# SparkFun_IR_Thermometer_Eval-MLX90614.net
KiCad netlist of a schematic drawn in EAGLE
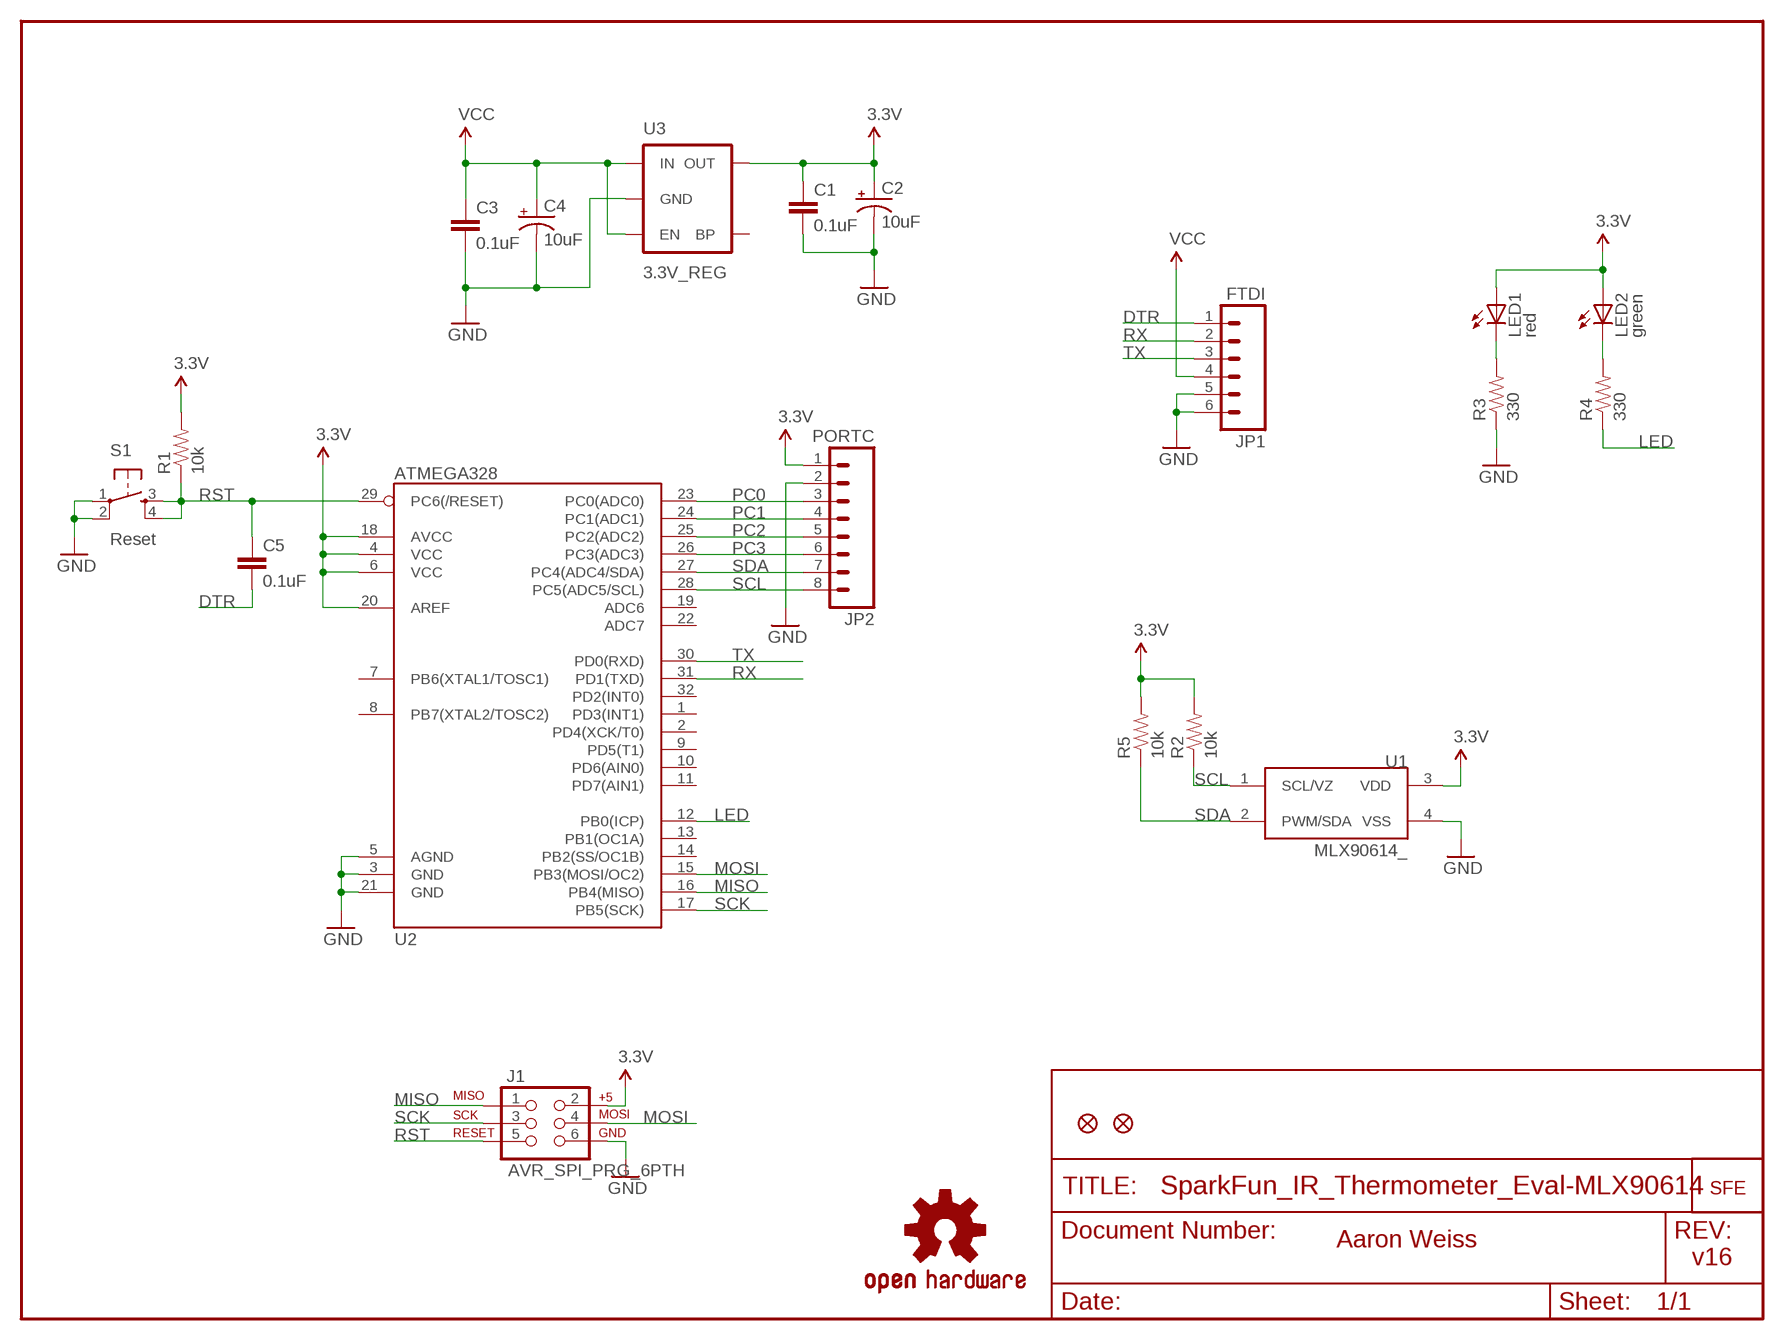
[diagram p0: schematic, sheet 1]

(export (version "E")
  (design (tool "Eeschema 10.0.6"))
  (components
    (comp (ref "C1")
      (value "0.1uF")
      (footprint "eagle-import:0402-CAP")
      (libsource (lib "eagle-import") (part "CAP0402-CAP"))
    )
    (comp (ref "C2")
      (value "10uF")
      (footprint "eagle-import:EIA3216")
      (libsource (lib "eagle-import") (part "CAP_POL1206"))
    )
    (comp (ref "C3")
      (value "0.1uF")
      (footprint "eagle-import:0402-CAP")
      (libsource (lib "eagle-import") (part "CAP0402-CAP"))
    )
    (comp (ref "C4")
      (value "10uF")
      (footprint "eagle-import:EIA3216")
      (libsource (lib "eagle-import") (part "CAP_POL1206"))
    )
    (comp (ref "C5")
      (value "0.1uF")
      (footprint "eagle-import:0402-CAP")
      (libsource (lib "eagle-import") (part "CAP0402-CAP"))
    )
    (comp (ref "J1")
      (value "AVR_SPI_PRG_6PTH")
      (footprint "eagle-import:2X3")
      (libsource (lib "eagle-import") (part "AVR_SPI_PRG_6PTH"))
    )
    (comp (ref "JP1")
      (value "FTDI")
      (footprint "eagle-import:1X06")
      (libsource (lib "eagle-import") (part "M06SIP"))
    )
    (comp (ref "JP2")
      (value "PORTC")
      (footprint "eagle-import:1X08")
      (libsource (lib "eagle-import") (part "M08"))
    )
    (comp (ref "JP3")
      (value "FIDUCIAL1X2.5")
      (footprint "eagle-import:FIDUCIAL-1X2.5")
      (libsource (lib "eagle-import") (part "FIDUCIAL1X2.5"))
    )
    (comp (ref "JP4")
      (value "LOGO-SFESK")
      (footprint "eagle-import:SFE-LOGO-FLAME")
      (libsource (lib "eagle-import") (part "LOGO-SFESK"))
    )
    (comp (ref "JP5")
      (value "FIDUCIAL1X2.5")
      (footprint "eagle-import:FIDUCIAL-1X2.5")
      (libsource (lib "eagle-import") (part "FIDUCIAL1X2.5"))
    )
    (comp (ref "LED1")
      (value "red")
      (footprint "eagle-import:LED-0603")
      (libsource (lib "eagle-import") (part "LED0603"))
    )
    (comp (ref "LED2")
      (value "green")
      (footprint "eagle-import:LED-0603")
      (libsource (lib "eagle-import") (part "LED0603"))
    )
    (comp (ref "R1")
      (value "10k")
      (footprint "eagle-import:0402-RES")
      (libsource (lib "eagle-import") (part "RESISTOR0402-RES"))
    )
    (comp (ref "R2")
      (value "10k")
      (footprint "eagle-import:0402-RES")
      (libsource (lib "eagle-import") (part "RESISTOR0402-RES"))
    )
    (comp (ref "R3")
      (value "330")
      (footprint "eagle-import:0402-RES")
      (libsource (lib "eagle-import") (part "RESISTOR0402-RES"))
    )
    (comp (ref "R4")
      (value "330")
      (footprint "eagle-import:0402-RES")
      (libsource (lib "eagle-import") (part "RESISTOR0402-RES"))
    )
    (comp (ref "R5")
      (value "10k")
      (footprint "eagle-import:0402-RES")
      (libsource (lib "eagle-import") (part "RESISTOR0402-RES"))
    )
    (comp (ref "S1")
      (value "Reset")
      (footprint "eagle-import:TACTILE_SWITCH_SMD")
      (libsource (lib "eagle-import") (part "TAC_SWITCHSMD"))
    )
    (comp (ref "U$1")
      (value "OSHW-LOGOS")
      (footprint "eagle-import:OSHW-LOGO-S")
      (libsource (lib "eagle-import") (part "OSHW-LOGOS"))
    )
    (comp (ref "U1")
      (value "MLX90614_")
      (footprint "eagle-import:TO-39")
      (libsource (lib "eagle-import") (part "MLX90614_"))
    )
    (comp (ref "U2")
      (value "ATMEGA328")
      (footprint "eagle-import:TQFP32-08")
      (libsource (lib "eagle-import") (part "ATMEGA168"))
    )
    (comp (ref "U3")
      (value "3.3V_REG")
      (footprint "eagle-import:SOT23-5")
      (libsource (lib "eagle-import") (part "V_REG_LDOSMD"))
    )
  )
  (nets
    (net (code "1") (name "/DTR") (class "Default")
      (node (ref "C5") (pin "2") (pinfunction "2_2") (pintype "passive"))
      (node (ref "JP1") (pin "1") (pinfunction "1_1") (pintype "passive"))
    )
    (net (code "2") (name "/LED") (class "Default")
      (node (ref "R4") (pin "1") (pinfunction "1_1") (pintype "passive"))
      (node (ref "U2") (pin "12") (pinfunction "PB0(ICP)_12") (pintype "bidirectional"))
    )
    (net (code "3") (name "/MISO") (class "Default")
      (node (ref "J1") (pin "1") (pinfunction "1_1") (pintype "passive"))
      (node (ref "U2") (pin "16") (pinfunction "PB4(MISO)_16") (pintype "bidirectional"))
    )
    (net (code "4") (name "/MOSI") (class "Default")
      (node (ref "J1") (pin "4") (pinfunction "4_4") (pintype "passive"))
      (node (ref "U2") (pin "15") (pinfunction "PB3(MOSI/OC2)_15") (pintype "bidirectional"))
    )
    (net (code "5") (name "/PC0") (class "Default")
      (node (ref "JP2") (pin "3") (pinfunction "3_3") (pintype "passive"))
      (node (ref "U2") (pin "23") (pinfunction "PC0(ADC0)_23") (pintype "bidirectional"))
    )
    (net (code "6") (name "/PC1") (class "Default")
      (node (ref "JP2") (pin "4") (pinfunction "4_4") (pintype "passive"))
      (node (ref "U2") (pin "24") (pinfunction "PC1(ADC1)_24") (pintype "bidirectional"))
    )
    (net (code "7") (name "/PC2") (class "Default")
      (node (ref "JP2") (pin "5") (pinfunction "5_5") (pintype "passive"))
      (node (ref "U2") (pin "25") (pinfunction "PC2(ADC2)_25") (pintype "bidirectional"))
    )
    (net (code "8") (name "/PC3") (class "Default")
      (node (ref "JP2") (pin "6") (pinfunction "6_6") (pintype "passive"))
      (node (ref "U2") (pin "26") (pinfunction "PC3(ADC3)_26") (pintype "bidirectional"))
    )
    (net (code "9") (name "/RST") (class "Default")
      (node (ref "C5") (pin "1") (pinfunction "1_1") (pintype "passive"))
      (node (ref "J1") (pin "5") (pinfunction "5_5") (pintype "passive"))
      (node (ref "R1") (pin "1") (pinfunction "1_1") (pintype "passive"))
      (node (ref "S1") (pin "3") (pinfunction "3_3") (pintype "passive"))
      (node (ref "S1") (pin "4") (pinfunction "4_4") (pintype "passive"))
      (node (ref "U2") (pin "29") (pinfunction "PC6(/RESET)_29") (pintype "bidirectional"))
    )
    (net (code "10") (name "/RX") (class "Default")
      (node (ref "JP1") (pin "2") (pinfunction "2_2") (pintype "passive"))
      (node (ref "U2") (pin "31") (pinfunction "PD1(TXD)_31") (pintype "bidirectional"))
    )
    (net (code "11") (name "/SCK") (class "Default")
      (node (ref "J1") (pin "3") (pinfunction "3_3") (pintype "passive"))
      (node (ref "U2") (pin "17") (pinfunction "PB5(SCK)_17") (pintype "bidirectional"))
    )
    (net (code "12") (name "/SCL") (class "Default")
      (node (ref "JP2") (pin "8") (pinfunction "8_8") (pintype "passive"))
      (node (ref "R2") (pin "1") (pinfunction "1_1") (pintype "passive"))
      (node (ref "U1") (pin "1") (pinfunction "SCL/VZ_1") (pintype "bidirectional"))
      (node (ref "U2") (pin "28") (pinfunction "PC5(ADC5/SCL)_28") (pintype "bidirectional"))
    )
    (net (code "13") (name "/SDA") (class "Default")
      (node (ref "JP2") (pin "7") (pinfunction "7_7") (pintype "passive"))
      (node (ref "R5") (pin "1") (pinfunction "1_1") (pintype "passive"))
      (node (ref "U1") (pin "2") (pinfunction "PWM/SDA_2") (pintype "bidirectional"))
      (node (ref "U2") (pin "27") (pinfunction "PC4(ADC4/SDA)_27") (pintype "bidirectional"))
    )
    (net (code "14") (name "/TX") (class "Default")
      (node (ref "JP1") (pin "3") (pinfunction "3_3") (pintype "passive"))
      (node (ref "U2") (pin "30") (pinfunction "PD0(RXD)_30") (pintype "bidirectional"))
    )
    (net (code "15") (name "3.3V") (class "Default")
      (node (ref "C1") (pin "1") (pinfunction "1_1") (pintype "passive"))
      (node (ref "C2") (pin "A") (pinfunction "+_A") (pintype "passive"))
      (node (ref "J1") (pin "2") (pinfunction "2_2") (pintype "passive"))
      (node (ref "JP2") (pin "1") (pinfunction "1_1") (pintype "passive"))
      (node (ref "LED1") (pin "A") (pinfunction "A_A") (pintype "passive"))
      (node (ref "LED2") (pin "A") (pinfunction "A_A") (pintype "passive"))
      (node (ref "R1") (pin "2") (pinfunction "2_2") (pintype "passive"))
      (node (ref "R2") (pin "2") (pinfunction "2_2") (pintype "passive"))
      (node (ref "R5") (pin "2") (pinfunction "2_2") (pintype "passive"))
      (node (ref "U1") (pin "3") (pinfunction "VDD_3") (pintype "bidirectional"))
      (node (ref "U2") (pin "18") (pinfunction "AVCC_18") (pintype "bidirectional"))
      (node (ref "U2") (pin "20") (pinfunction "AREF_20") (pintype "bidirectional"))
      (node (ref "U2") (pin "4") (pinfunction "VCC_4") (pintype "bidirectional"))
      (node (ref "U2") (pin "6") (pinfunction "VCC_6") (pintype "bidirectional"))
      (node (ref "U3") (pin "5") (pinfunction "OUT_5") (pintype "passive"))
    )
    (net (code "16") (name "GND") (class "Default")
      (node (ref "C1") (pin "2") (pinfunction "2_2") (pintype "passive"))
      (node (ref "C2") (pin "C") (pinfunction "-_C") (pintype "passive"))
      (node (ref "C3") (pin "2") (pinfunction "2_2") (pintype "passive"))
      (node (ref "C4") (pin "C") (pinfunction "-_C") (pintype "passive"))
      (node (ref "J1") (pin "6") (pinfunction "6_6") (pintype "passive"))
      (node (ref "JP1") (pin "5") (pinfunction "5_5") (pintype "passive"))
      (node (ref "JP1") (pin "6") (pinfunction "6_6") (pintype "passive"))
      (node (ref "JP2") (pin "2") (pinfunction "2_2") (pintype "passive"))
      (node (ref "R3") (pin "1") (pinfunction "1_1") (pintype "passive"))
      (node (ref "S1") (pin "1") (pinfunction "1_1") (pintype "passive"))
      (node (ref "S1") (pin "2") (pinfunction "2_2") (pintype "passive"))
      (node (ref "U1") (pin "4") (pinfunction "VSS_4") (pintype "bidirectional"))
      (node (ref "U2") (pin "21") (pinfunction "GND_21") (pintype "bidirectional"))
      (node (ref "U2") (pin "3") (pinfunction "GND_3") (pintype "bidirectional"))
      (node (ref "U2") (pin "5") (pinfunction "AGND_5") (pintype "bidirectional"))
      (node (ref "U3") (pin "2") (pinfunction "GND_2") (pintype "input"))
    )
    (net (code "17") (name "Net-(LED1-PadC)") (class "Default")
      (node (ref "LED1") (pin "C") (pinfunction "C_C") (pintype "passive"))
      (node (ref "R3") (pin "2") (pinfunction "2_2") (pintype "passive"))
    )
    (net (code "18") (name "Net-(LED2-PadC)") (class "Default")
      (node (ref "LED2") (pin "C") (pinfunction "C_C") (pintype "passive"))
      (node (ref "R4") (pin "2") (pinfunction "2_2") (pintype "passive"))
    )
    (net (code "19") (name "VCC") (class "Default")
      (node (ref "C3") (pin "1") (pinfunction "1_1") (pintype "passive"))
      (node (ref "C4") (pin "A") (pinfunction "+_A") (pintype "passive"))
      (node (ref "JP1") (pin "4") (pinfunction "4_4") (pintype "passive"))
      (node (ref "U3") (pin "1") (pinfunction "IN_1") (pintype "input"))
      (node (ref "U3") (pin "3") (pinfunction "EN_3") (pintype "input"))
    )
    (net (code "20") (name "unconnected-(U2-ADC6-Pad19)") (class "Default")
      (node (ref "U2") (pin "19") (pinfunction "ADC6_19") (pintype "bidirectional"))
    )
    (net (code "21") (name "unconnected-(U2-ADC7-Pad22)") (class "Default")
      (node (ref "U2") (pin "22") (pinfunction "ADC7_22") (pintype "bidirectional"))
    )
    (net (code "22") (name "unconnected-(U2-PB1(OC1A)-Pad13)") (class "Default")
      (node (ref "U2") (pin "13") (pinfunction "PB1(OC1A)_13") (pintype "bidirectional"))
    )
    (net (code "23") (name "unconnected-(U2-PB2(SS{slash}OC1B)-Pad14)") (class "Default")
      (node (ref "U2") (pin "14") (pinfunction "PB2(SS/OC1B)_14") (pintype "bidirectional"))
    )
    (net (code "24") (name "unconnected-(U2-PB6(XTAL1{slash}TOSC1)-Pad7)") (class "Default")
      (node (ref "U2") (pin "7") (pinfunction "PB6(XTAL1/TOSC1)_7") (pintype "bidirectional"))
    )
    (net (code "25") (name "unconnected-(U2-PB7(XTAL2{slash}TOSC2)-Pad8)") (class "Default")
      (node (ref "U2") (pin "8") (pinfunction "PB7(XTAL2/TOSC2)_8") (pintype "bidirectional"))
    )
    (net (code "26") (name "unconnected-(U2-PD2(INT0)-Pad32)") (class "Default")
      (node (ref "U2") (pin "32") (pinfunction "PD2(INT0)_32") (pintype "bidirectional"))
    )
    (net (code "27") (name "unconnected-(U2-PD3(INT1)-Pad1)") (class "Default")
      (node (ref "U2") (pin "1") (pinfunction "PD3(INT1)_1") (pintype "bidirectional"))
    )
    (net (code "28") (name "unconnected-(U2-PD4(XCK{slash}T0)-Pad2)") (class "Default")
      (node (ref "U2") (pin "2") (pinfunction "PD4(XCK/T0)_2") (pintype "bidirectional"))
    )
    (net (code "29") (name "unconnected-(U2-PD5(T1)-Pad9)") (class "Default")
      (node (ref "U2") (pin "9") (pinfunction "PD5(T1)_9") (pintype "bidirectional"))
    )
    (net (code "30") (name "unconnected-(U2-PD6(AIN0)-Pad10)") (class "Default")
      (node (ref "U2") (pin "10") (pinfunction "PD6(AIN0)_10") (pintype "bidirectional"))
    )
    (net (code "31") (name "unconnected-(U2-PD7(AIN1)-Pad11)") (class "Default")
      (node (ref "U2") (pin "11") (pinfunction "PD7(AIN1)_11") (pintype "bidirectional"))
    )
    (net (code "32") (name "unconnected-(U3-BP-Pad4)") (class "Default")
      (node (ref "U3") (pin "4") (pinfunction "BP_4") (pintype "input"))
    )
  )
)
